# Pt100-Amplifier-LM324.net
KiCad netlist of a schematic drawn in EAGLE
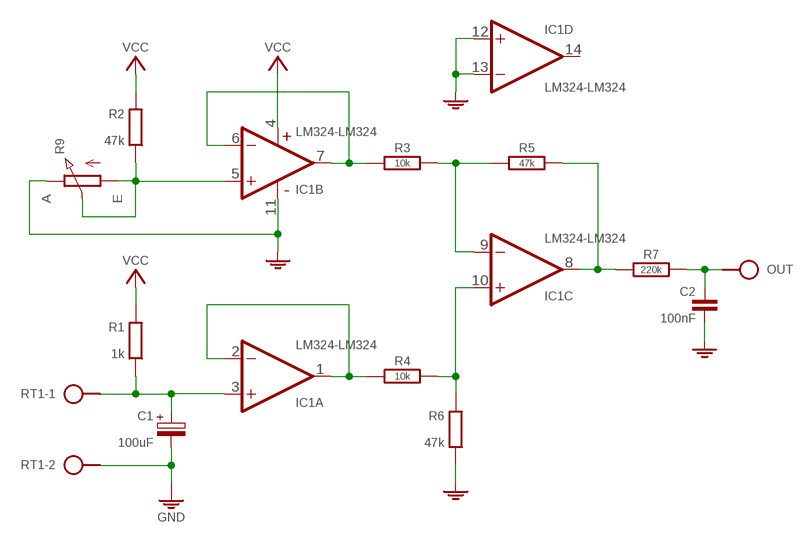
[diagram p0: schematic, sheet 1]

(export (version "E")
  (design (tool "Eeschema 10.0.6"))
  (components
    (comp (ref "C1")
      (value "100uF")
      (footprint "eagle-import:E2,5-5")
      (libsource (lib "eagle-import") (part "CPOLE2.5-5"))
    )
    (comp (ref "C2")
      (value "100nF")
      (footprint "eagle-import:C050-020X044_V")
      (libsource (lib "eagle-import") (part "C050-020X044/V"))
    )
    (comp (ref "IC1")
      (value "LM324-LM324")
      (footprint "eagle-import:DIL14-LM324")
      (libsource (lib "eagle-import") (part "LM324-LM324"))
    )
    (comp (ref "OUT")
      (value "HPORT")
      (footprint "eagle-import:SPAD")
      (libsource (lib "eagle-import") (part "HPORT"))
    )
    (comp (ref "R1")
      (value "1k")
      (footprint "eagle-import:0204_10")
      (libsource (lib "eagle-import") (part "R0204/10"))
    )
    (comp (ref "R2")
      (value "47k")
      (footprint "eagle-import:0204_10")
      (libsource (lib "eagle-import") (part "R0204/10"))
    )
    (comp (ref "R3")
      (value "10k")
      (footprint "eagle-import:0204_10-V")
      (libsource (lib "eagle-import") (part "R-H0204/10-V"))
    )
    (comp (ref "R4")
      (value "10k")
      (footprint "eagle-import:0204_15")
      (libsource (lib "eagle-import") (part "R-H0204/15"))
    )
    (comp (ref "R5")
      (value "47k")
      (footprint "eagle-import:0204_10-V")
      (libsource (lib "eagle-import") (part "R-H0204/10-V"))
    )
    (comp (ref "R6")
      (value "47k")
      (footprint "eagle-import:0204_10-V")
      (libsource (lib "eagle-import") (part "R0204/10-V"))
    )
    (comp (ref "R7")
      (value "220k")
      (footprint "eagle-import:0204_10")
      (libsource (lib "eagle-import") (part "R-H0204/10"))
    )
    (comp (ref "R9")
      (value "POT")
      (footprint "eagle-import:POT")
      (libsource (lib "eagle-import") (part "POT"))
    )
    (comp (ref "RT1")
      (value "SPAD-2")
      (footprint "eagle-import:SPAD-2")
      (libsource (lib "eagle-import") (part "SPAD-2"))
    )
    (comp (ref "S5")
      (value "VCC_GNDPWR-L")
      (footprint "eagle-import:PWR-L")
      (libsource (lib "eagle-import") (part "VCC_GNDPWR-L"))
    )
  )
  (nets
    (net (code "1") (name "GND") (class "Default")
      (node (ref "C1") (pin "-") (pinfunction "-_-") (pintype "passive"))
      (node (ref "C2") (pin "2") (pinfunction "2_2") (pintype "passive"))
      (node (ref "IC1") (pin "11") (pinfunction "V-_11") (pintype "power_in"))
      (node (ref "IC1") (pin "12") (pinfunction "+IN_12") (pintype "input"))
      (node (ref "IC1") (pin "13") (pinfunction "-IN_13") (pintype "input"))
      (node (ref "R6") (pin "2") (pinfunction "1_2") (pintype "passive"))
      (node (ref "R9") (pin "E") (pinfunction "E_E") (pintype "passive"))
      (node (ref "RT1") (pin "2") (pinfunction "P$1_2") (pintype "passive"))
      (node (ref "S5") (pin "1") (pinfunction "GND_1") (pintype "power_in"))
    )
    (net (code "2") (name "Net-(IC1A-+IN)") (class "Default")
      (node (ref "C1") (pin "+") (pinfunction "+_+") (pintype "passive"))
      (node (ref "IC1") (pin "3") (pinfunction "+IN_3") (pintype "input"))
      (node (ref "R1") (pin "2") (pinfunction "1_2") (pintype "passive"))
      (node (ref "RT1") (pin "1") (pinfunction "P$1_1") (pintype "passive"))
    )
    (net (code "3") (name "Net-(IC1A--IN)") (class "Default")
      (node (ref "IC1") (pin "1") (pinfunction "OUT_1") (pintype "output"))
      (node (ref "IC1") (pin "2") (pinfunction "-IN_2") (pintype "input"))
      (node (ref "R4") (pin "1") (pinfunction "1_1") (pintype "passive"))
    )
    (net (code "4") (name "Net-(IC1B-+IN)") (class "Default")
      (node (ref "IC1") (pin "5") (pinfunction "+IN_5") (pintype "input"))
      (node (ref "R2") (pin "2") (pinfunction "1_2") (pintype "passive"))
      (node (ref "R9") (pin "A") (pinfunction "A_A") (pintype "passive"))
      (node (ref "R9") (pin "S") (pinfunction "S_S") (pintype "passive"))
    )
    (net (code "5") (name "Net-(IC1B--IN)") (class "Default")
      (node (ref "IC1") (pin "6") (pinfunction "-IN_6") (pintype "input"))
      (node (ref "IC1") (pin "7") (pinfunction "OUT_7") (pintype "output"))
      (node (ref "R3") (pin "1") (pinfunction "1_1") (pintype "passive"))
    )
    (net (code "6") (name "Net-(IC1C-+IN)") (class "Default")
      (node (ref "IC1") (pin "10") (pinfunction "+IN_10") (pintype "input"))
      (node (ref "R4") (pin "2") (pinfunction "2_2") (pintype "passive"))
      (node (ref "R6") (pin "1") (pinfunction "2_1") (pintype "passive"))
    )
    (net (code "7") (name "Net-(IC1C--IN)") (class "Default")
      (node (ref "IC1") (pin "9") (pinfunction "-IN_9") (pintype "input"))
      (node (ref "R3") (pin "2") (pinfunction "2_2") (pintype "passive"))
      (node (ref "R5") (pin "1") (pinfunction "1_1") (pintype "passive"))
    )
    (net (code "8") (name "Net-(IC1C-OUT)") (class "Default")
      (node (ref "IC1") (pin "8") (pinfunction "OUT_8") (pintype "output"))
      (node (ref "R5") (pin "2") (pinfunction "2_2") (pintype "passive"))
      (node (ref "R7") (pin "1") (pinfunction "1_1") (pintype "passive"))
    )
    (net (code "9") (name "Net-(OUT-P$1)") (class "Default")
      (node (ref "C2") (pin "1") (pinfunction "1_1") (pintype "passive"))
      (node (ref "OUT") (pin "1") (pinfunction "P$1_1") (pintype "passive"))
      (node (ref "R7") (pin "2") (pinfunction "2_2") (pintype "passive"))
    )
    (net (code "10") (name "VCC") (class "Default")
      (node (ref "IC1") (pin "4") (pinfunction "V+_4") (pintype "power_in"))
      (node (ref "R1") (pin "1") (pinfunction "2_1") (pintype "passive"))
      (node (ref "R2") (pin "1") (pinfunction "2_1") (pintype "passive"))
      (node (ref "S5") (pin "2") (pinfunction "VCC_2") (pintype "power_in"))
    )
    (net (code "11") (name "unconnected-(IC1D-OUT-Pad14)") (class "Default")
      (node (ref "IC1") (pin "14") (pinfunction "OUT_14") (pintype "output"))
    )
  )
)
